# oLoRa-part-GPS.net
KiCad netlist of a schematic drawn in EasyEDA
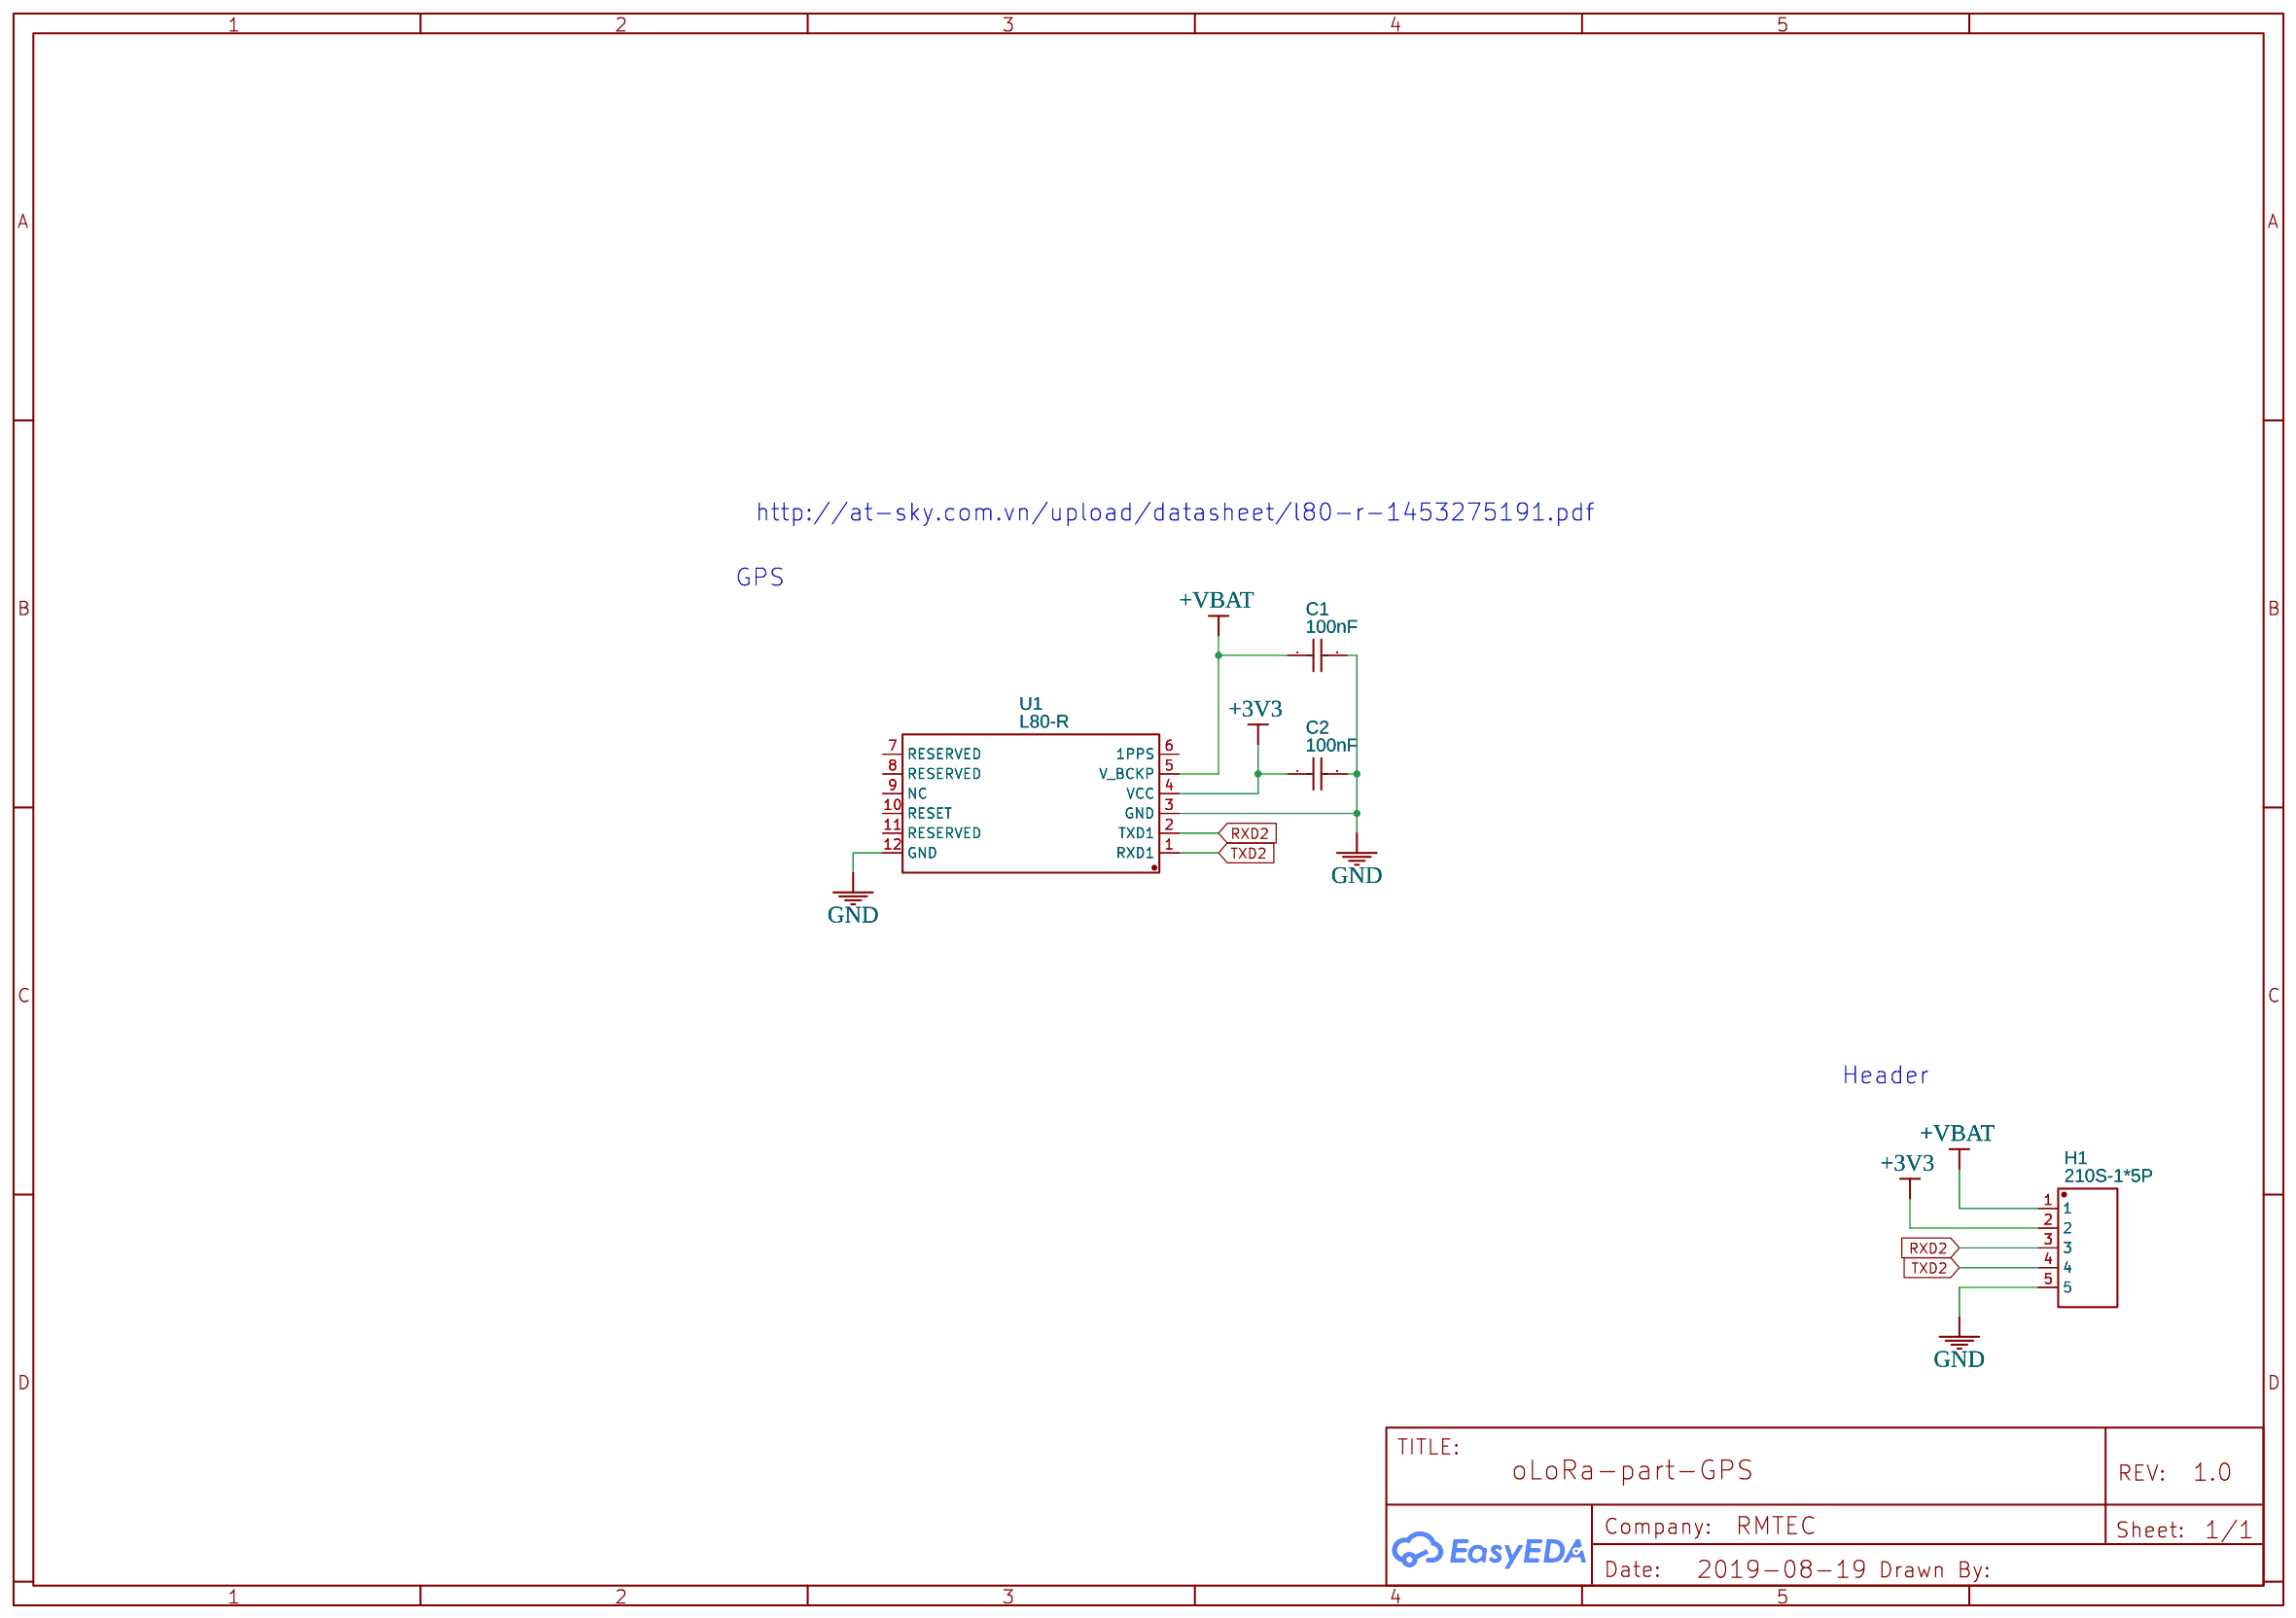
[diagram p0: schematic sheet]

(export (version "E")
  (design (tool "Eeschema 10.0.6"))
  (components
    (comp (ref "C1")
      (value "100nF")
      (fields
        (field (name "BOM_Manufacturer Part") "0603B104K500NT")
        (field (name "BOM_Supplier Part") "C30926")
      )
      (libsource (lib "") (part "0603B104K500NT"))
    )
    (comp (ref "C2")
      (value "100nF")
      (fields
        (field (name "BOM_Manufacturer Part") "0603B104K500NT")
        (field (name "BOM_Supplier Part") "C30926")
      )
      (libsource (lib "") (part "0603B104K500NT"))
    )
    (comp (ref "H1")
      (value "210S-1*5P")
      (fields
        (field (name "BOM_Manufacturer Part") "210S-1*5P L=11.6MMGold-plated black")
        (field (name "BOM_Supplier Part") "C124379")
      )
      (libsource (lib "") (part "Unknown_1045_625"))
    )
    (comp (ref "U1")
      (value "L80-R")
      (fields (field (name "BOM_Supplier Part") "C188357"))
      (libsource (lib "") (part "Unknown_515_400"))
    )
  )
  (nets
    (net (code "1") (name "+3V3") (class "Default")
      (node (ref "C2") (pin "2") (pinfunction "2_2") (pintype "input"))
      (node (ref "H1") (pin "2") (pinfunction "2_2") (pintype "unspecified"))
      (node (ref "U1") (pin "4") (pinfunction "VCC_4") (pintype "unspecified"))
    )
    (net (code "2") (name "+VBAT") (class "Default")
      (node (ref "C1") (pin "2") (pinfunction "2_2") (pintype "input"))
      (node (ref "H1") (pin "1") (pinfunction "1_1") (pintype "unspecified"))
      (node (ref "U1") (pin "5") (pinfunction "V_BCKP_5") (pintype "unspecified"))
    )
    (net (code "3") (name "GND") (class "Default")
      (node (ref "C1") (pin "1") (pinfunction "1_1") (pintype "input"))
      (node (ref "C2") (pin "1") (pinfunction "1_1") (pintype "input"))
      (node (ref "H1") (pin "5") (pinfunction "5_5") (pintype "unspecified"))
      (node (ref "U1") (pin "12") (pinfunction "GND_12") (pintype "unspecified"))
      (node (ref "U1") (pin "3") (pinfunction "GND_3") (pintype "unspecified"))
    )
    (net (code "4") (name "RXD2") (class "Default")
      (node (ref "H1") (pin "3") (pinfunction "3_3") (pintype "unspecified"))
      (node (ref "U1") (pin "2") (pinfunction "TXD1_2") (pintype "unspecified"))
    )
    (net (code "5") (name "TXD2") (class "Default")
      (node (ref "H1") (pin "4") (pinfunction "4_4") (pintype "unspecified"))
      (node (ref "U1") (pin "1") (pinfunction "RXD1_1") (pintype "unspecified"))
    )
    (net (code "6") (name "unconnected-(U1-1PPS-Pad6)") (class "Default")
      (node (ref "U1") (pin "6") (pinfunction "1PPS_6") (pintype "unspecified"))
    )
    (net (code "7") (name "unconnected-(U1-NC-Pad9)") (class "Default")
      (node (ref "U1") (pin "9") (pinfunction "NC_9") (pintype "unspecified"))
    )
    (net (code "8") (name "unconnected-(U1-RESERVED-Pad7)") (class "Default")
      (node (ref "U1") (pin "7") (pinfunction "RESERVED_7") (pintype "unspecified"))
    )
    (net (code "9") (name "unconnected-(U1-RESERVED-Pad8)") (class "Default")
      (node (ref "U1") (pin "8") (pinfunction "RESERVED_8") (pintype "unspecified"))
    )
    (net (code "10") (name "unconnected-(U1-RESERVED-Pad11)") (class "Default")
      (node (ref "U1") (pin "11") (pinfunction "RESERVED_11") (pintype "unspecified"))
    )
    (net (code "11") (name "unconnected-(U1-RESET-Pad10)") (class "Default")
      (node (ref "U1") (pin "10") (pinfunction "RESET_10") (pintype "unspecified"))
    )
  )
)
